# schmatic.net
KiCad netlist of a schematic drawn in EAGLE
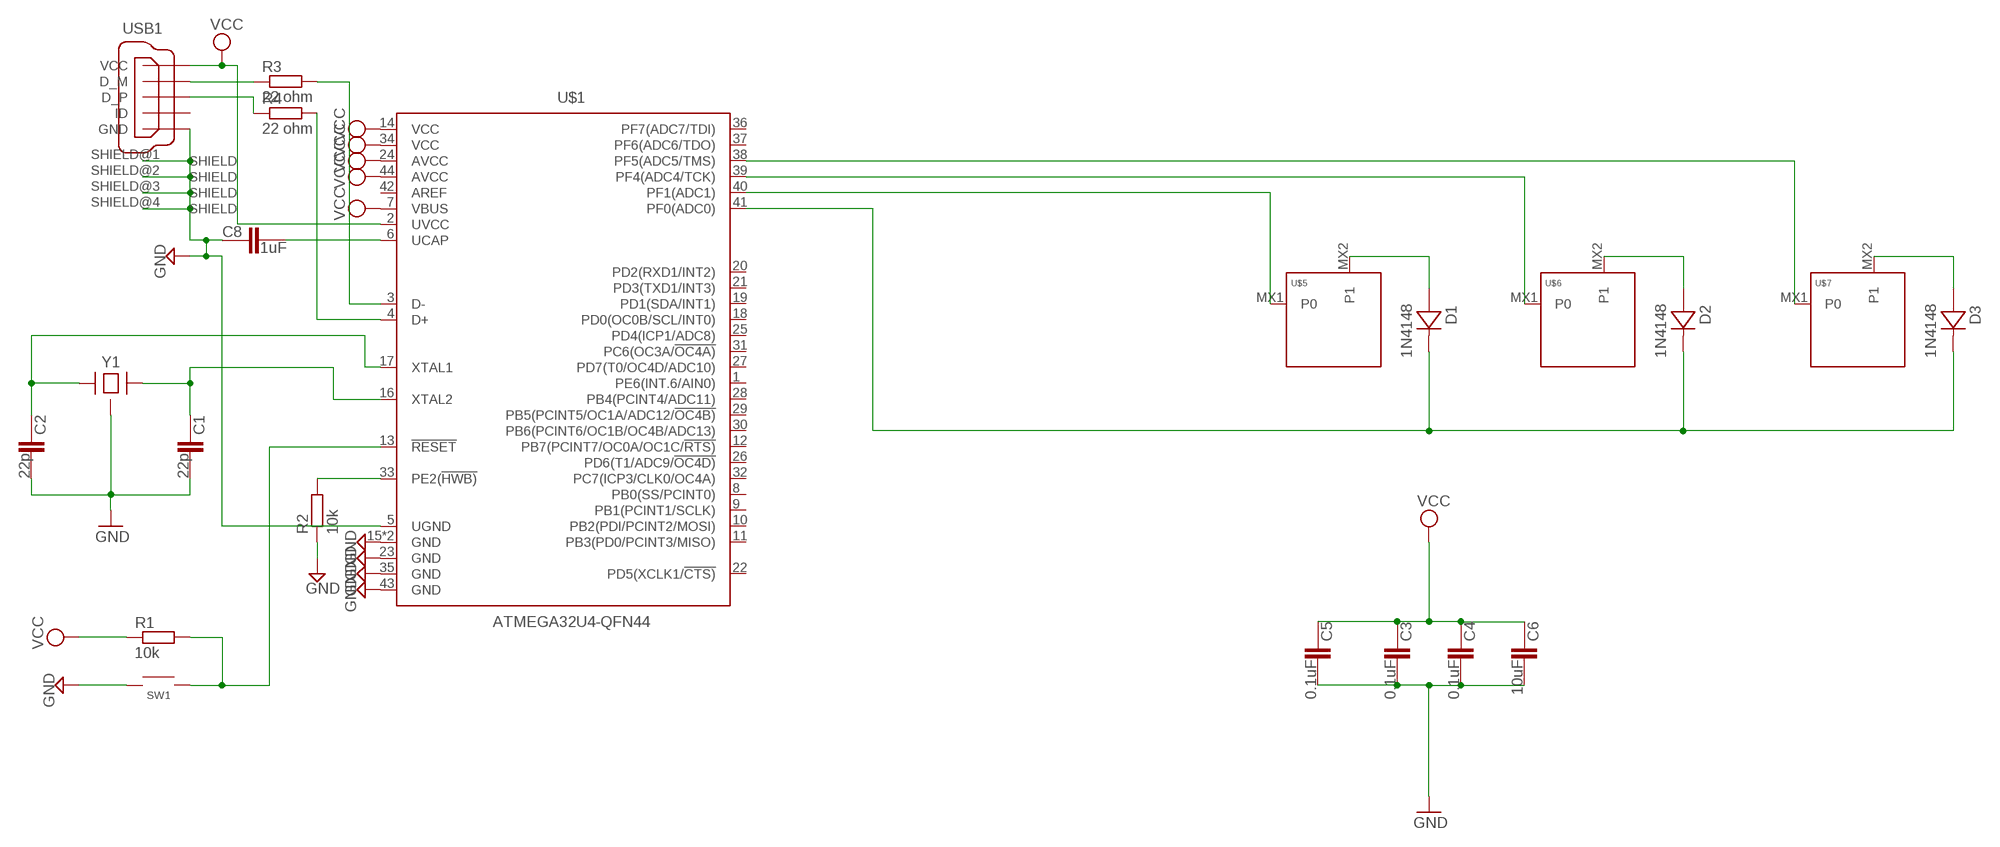
[diagram p0: schematic, sheet 1]

(export (version "E")
  (design (tool "Eeschema 10.0.6"))
  (components
    (comp (ref "C1")
      (value "22p")
      (footprint "eagle-import:C0402")
      (libsource (lib "eagle-import") (part "CAPACITOR-0402"))
    )
    (comp (ref "C2")
      (value "22p")
      (footprint "eagle-import:C0402")
      (libsource (lib "eagle-import") (part "CAPACITOR-0402"))
    )
    (comp (ref "C3")
      (value "0.1uF")
      (footprint "eagle-import:C0402")
      (libsource (lib "eagle-import") (part "CAPACITOR-0402"))
    )
    (comp (ref "C4")
      (value "0.1uF")
      (footprint "eagle-import:C0402")
      (libsource (lib "eagle-import") (part "CAPACITOR-0402"))
    )
    (comp (ref "C5")
      (value "0.1uF")
      (footprint "eagle-import:C0402")
      (libsource (lib "eagle-import") (part "CAPACITOR-0402"))
    )
    (comp (ref "C6")
      (value "10uF")
      (footprint "eagle-import:C0402")
      (libsource (lib "eagle-import") (part "CAPACITOR-0402"))
    )
    (comp (ref "C8")
      (value "1uF")
      (footprint "eagle-import:C0402")
      (libsource (lib "eagle-import") (part "CAPACITOR-0402"))
    )
    (comp (ref "D1")
      (value "1N4148")
      (footprint "eagle-import:DO-35")
      (libsource (lib "eagle-import") (part "DIODE-DO-35"))
    )
    (comp (ref "D2")
      (value "1N4148")
      (footprint "eagle-import:DO-35")
      (libsource (lib "eagle-import") (part "DIODE-DO-35"))
    )
    (comp (ref "D3")
      (value "1N4148")
      (footprint "eagle-import:DO-35")
      (libsource (lib "eagle-import") (part "DIODE-DO-35"))
    )
    (comp (ref "R1")
      (value "10k")
      (footprint "eagle-import:R0402")
      (libsource (lib "eagle-import") (part "RESISTOR-0405"))
    )
    (comp (ref "R2")
      (value "10k")
      (footprint "eagle-import:R0402")
      (libsource (lib "eagle-import") (part "RESISTOR-0405"))
    )
    (comp (ref "R3")
      (value "22 ohm")
      (footprint "eagle-import:R0402")
      (libsource (lib "eagle-import") (part "RESISTOR-0405"))
    )
    (comp (ref "R4")
      (value "22 ohm")
      (footprint "eagle-import:R0402")
      (libsource (lib "eagle-import") (part "RESISTOR-0405"))
    )
    (comp (ref "SW1")
      (value "SWITCH-SMD-EVQP-P2602W")
      (footprint "eagle-import:SWITCH-SMD-EVQP-P2602W")
      (libsource (lib "eagle-import") (part "SWITCH-SMD-EVQP-P2602W"))
    )
    (comp (ref "U$1")
      (value "ATMEGA32U4-QFN44")
      (footprint "eagle-import:QFN-44")
      (libsource (lib "eagle-import") (part "ATMEGA32U4-QFN44"))
    )
    (comp (ref "U$5")
      (value "KEYSWITCH-PLAIN-MXHSPCB-1U")
      (footprint "eagle-import:MXHSPCB-1U")
      (libsource (lib "eagle-import") (part "KEYSWITCH-PLAIN-MXHSPCB-1U"))
    )
    (comp (ref "U$6")
      (value "KEYSWITCH-PLAIN-MXHSPCB-1U")
      (footprint "eagle-import:MXHSPCB-1U")
      (libsource (lib "eagle-import") (part "KEYSWITCH-PLAIN-MXHSPCB-1U"))
    )
    (comp (ref "U$7")
      (value "KEYSWITCH-PLAIN-MXHSPCB-1U")
      (footprint "eagle-import:MXHSPCB-1U")
      (libsource (lib "eagle-import") (part "KEYSWITCH-PLAIN-MXHSPCB-1U"))
    )
    (comp (ref "USB1")
      (value "USB_CONN-MICRO-FEMALE")
      (footprint "eagle-import:ZB62D-B-5PA8")
      (libsource (lib "eagle-import") (part "USB_CONN-MICRO-FEMALE"))
    )
    (comp (ref "Y1")
      (value "CRYSTAL-4PIN-3.2X2.5")
      (footprint "eagle-import:CRYSTAL-3.2X2.5")
      (libsource (lib "eagle-import") (part "CRYSTAL-4PIN-3.2X2.5"))
    )
  )
  (nets
    (net (code "1") (name "GND") (class "Default")
      (node (ref "C1") (pin "2") (pinfunction "2_2") (pintype "passive"))
      (node (ref "C2") (pin "2") (pinfunction "2_2") (pintype "passive"))
      (node (ref "C3") (pin "2") (pinfunction "2_2") (pintype "passive"))
      (node (ref "C4") (pin "2") (pinfunction "2_2") (pintype "passive"))
      (node (ref "C5") (pin "2") (pinfunction "2_2") (pintype "passive"))
      (node (ref "C6") (pin "2") (pinfunction "2_2") (pintype "passive"))
      (node (ref "C8") (pin "1") (pinfunction "1_1") (pintype "passive"))
      (node (ref "R2") (pin "1") (pinfunction "1_1") (pintype "passive"))
      (node (ref "SW1") (pin "1A") (pinfunction "1_1A") (pintype "passive"))
      (node (ref "SW1") (pin "1B") (pinfunction "1_1B") (pintype "passive"))
      (node (ref "U$1") (pin "15") (pinfunction "GND_15") (pintype "bidirectional"))
      (node (ref "U$1") (pin "23") (pinfunction "GND_23") (pintype "bidirectional"))
      (node (ref "U$1") (pin "35") (pinfunction "GND_35") (pintype "bidirectional"))
      (node (ref "U$1") (pin "43") (pinfunction "GND_43") (pintype "bidirectional"))
      (node (ref "U$1") (pin "5") (pinfunction "UGND_5") (pintype "bidirectional"))
      (node (ref "U$1") (pin "TAB") (pinfunction "GND_TAB") (pintype "bidirectional"))
      (node (ref "USB1") (pin "5") (pinfunction "GND_5") (pintype "input"))
      (node (ref "USB1") (pin "SHIELD@1") (pinfunction "SHIELD_SHIELD@1") (pintype "bidirectional"))
      (node (ref "USB1") (pin "SHIELD@2") (pinfunction "SHIELD_SHIELD@2") (pintype "bidirectional"))
      (node (ref "USB1") (pin "SHIELD@3") (pinfunction "SHIELD_SHIELD@3") (pintype "bidirectional"))
      (node (ref "USB1") (pin "SHIELD@4") (pinfunction "SHIELD_SHIELD@4") (pintype "bidirectional"))
      (node (ref "Y1") (pin "2") (pinfunction "GND_2") (pintype "bidirectional"))
      (node (ref "Y1") (pin "4") (pinfunction "GND_4") (pintype "bidirectional"))
    )
    (net (code "2") (name "Net-(U$1-D+)") (class "Default")
      (node (ref "R4") (pin "2") (pinfunction "2_2") (pintype "passive"))
      (node (ref "U$1") (pin "4") (pinfunction "D+_4") (pintype "bidirectional"))
    )
    (net (code "3") (name "Net-(U$1-D-)") (class "Default")
      (node (ref "R3") (pin "2") (pinfunction "2_2") (pintype "passive"))
      (node (ref "U$1") (pin "3") (pinfunction "D-_3") (pintype "bidirectional"))
    )
    (net (code "4") (name "Net-(U$1-PE2(~{HWB}))") (class "Default")
      (node (ref "R2") (pin "2") (pinfunction "2_2") (pintype "passive"))
      (node (ref "U$1") (pin "33") (pinfunction "PE2(~{HWB})_33") (pintype "bidirectional"))
    )
    (net (code "5") (name "Net-(U$1-PF0(ADC0))") (class "Default")
      (node (ref "D1") (pin "C") (pinfunction "C_C") (pintype "passive"))
      (node (ref "D2") (pin "C") (pinfunction "C_C") (pintype "passive"))
      (node (ref "D3") (pin "C") (pinfunction "C_C") (pintype "passive"))
      (node (ref "U$1") (pin "41") (pinfunction "PF0(ADC0)_41") (pintype "bidirectional"))
    )
    (net (code "6") (name "Net-(U$1-PF1(ADC1))") (class "Default")
      (node (ref "U$1") (pin "40") (pinfunction "PF1(ADC1)_40") (pintype "bidirectional"))
      (node (ref "U$5") (pin "MX1") (pinfunction "P0_MX1") (pintype "bidirectional"))
    )
    (net (code "7") (name "Net-(U$1-PF4(ADC4{slash}TCK))") (class "Default")
      (node (ref "U$1") (pin "39") (pinfunction "PF4(ADC4/TCK)_39") (pintype "bidirectional"))
      (node (ref "U$6") (pin "MX1") (pinfunction "P0_MX1") (pintype "bidirectional"))
    )
    (net (code "8") (name "Net-(U$1-PF5(ADC5{slash}TMS))") (class "Default")
      (node (ref "U$1") (pin "38") (pinfunction "PF5(ADC5/TMS)_38") (pintype "bidirectional"))
      (node (ref "U$7") (pin "MX1") (pinfunction "P0_MX1") (pintype "bidirectional"))
    )
    (net (code "9") (name "Net-(U$1-UCAP)") (class "Default")
      (node (ref "C8") (pin "2") (pinfunction "2_2") (pintype "passive"))
      (node (ref "U$1") (pin "6") (pinfunction "UCAP_6") (pintype "bidirectional"))
    )
    (net (code "10") (name "Net-(U$1-XTAL1)") (class "Default")
      (node (ref "C2") (pin "1") (pinfunction "1_1") (pintype "passive"))
      (node (ref "U$1") (pin "17") (pinfunction "XTAL1_17") (pintype "bidirectional"))
      (node (ref "Y1") (pin "1") (pinfunction "1_1") (pintype "passive"))
    )
    (net (code "11") (name "Net-(U$1-XTAL2)") (class "Default")
      (node (ref "C1") (pin "1") (pinfunction "1_1") (pintype "passive"))
      (node (ref "U$1") (pin "16") (pinfunction "XTAL2_16") (pintype "bidirectional"))
      (node (ref "Y1") (pin "3") (pinfunction "2_3") (pintype "passive"))
    )
    (net (code "12") (name "Net-(U$1-~{RESET})") (class "Default")
      (node (ref "R1") (pin "2") (pinfunction "2_2") (pintype "passive"))
      (node (ref "SW1") (pin "2A") (pinfunction "2_2A") (pintype "passive"))
      (node (ref "SW1") (pin "2B") (pinfunction "2_2B") (pintype "passive"))
      (node (ref "U$1") (pin "13") (pinfunction "~{RESET}_13") (pintype "bidirectional"))
    )
    (net (code "13") (name "Net-(U$5-P1)") (class "Default")
      (node (ref "D1") (pin "A") (pinfunction "A_A") (pintype "passive"))
      (node (ref "U$5") (pin "MX2") (pinfunction "P1_MX2") (pintype "bidirectional"))
    )
    (net (code "14") (name "Net-(U$6-P1)") (class "Default")
      (node (ref "D2") (pin "A") (pinfunction "A_A") (pintype "passive"))
      (node (ref "U$6") (pin "MX2") (pinfunction "P1_MX2") (pintype "bidirectional"))
    )
    (net (code "15") (name "Net-(U$7-P1)") (class "Default")
      (node (ref "D3") (pin "A") (pinfunction "A_A") (pintype "passive"))
      (node (ref "U$7") (pin "MX2") (pinfunction "P1_MX2") (pintype "bidirectional"))
    )
    (net (code "16") (name "Net-(USB1-D_M)") (class "Default")
      (node (ref "R3") (pin "1") (pinfunction "1_1") (pintype "passive"))
      (node (ref "USB1") (pin "2") (pinfunction "D_M_2") (pintype "input"))
    )
    (net (code "17") (name "Net-(USB1-D_P)") (class "Default")
      (node (ref "R4") (pin "1") (pinfunction "1_1") (pintype "passive"))
      (node (ref "USB1") (pin "3") (pinfunction "D_P_3") (pintype "input"))
    )
    (net (code "18") (name "VCC") (class "Default")
      (node (ref "C3") (pin "1") (pinfunction "1_1") (pintype "passive"))
      (node (ref "C4") (pin "1") (pinfunction "1_1") (pintype "passive"))
      (node (ref "C5") (pin "1") (pinfunction "1_1") (pintype "passive"))
      (node (ref "C6") (pin "1") (pinfunction "1_1") (pintype "passive"))
      (node (ref "R1") (pin "1") (pinfunction "1_1") (pintype "passive"))
      (node (ref "U$1") (pin "14") (pinfunction "VCC_14") (pintype "bidirectional"))
      (node (ref "U$1") (pin "2") (pinfunction "UVCC_2") (pintype "bidirectional"))
      (node (ref "U$1") (pin "24") (pinfunction "AVCC_24") (pintype "bidirectional"))
      (node (ref "U$1") (pin "34") (pinfunction "VCC_34") (pintype "bidirectional"))
      (node (ref "U$1") (pin "44") (pinfunction "AVCC_44") (pintype "bidirectional"))
      (node (ref "U$1") (pin "7") (pinfunction "VBUS_7") (pintype "bidirectional"))
      (node (ref "USB1") (pin "1") (pinfunction "VCC_1") (pintype "input"))
    )
    (net (code "19") (name "unconnected-(U$1-AREF-Pad42)") (class "Default")
      (node (ref "U$1") (pin "42") (pinfunction "AREF_42") (pintype "bidirectional"))
    )
    (net (code "20") (name "unconnected-(U$1-PB0(SS{slash}PCINT0)-Pad8)") (class "Default")
      (node (ref "U$1") (pin "8") (pinfunction "PB0(SS/PCINT0)_8") (pintype "bidirectional"))
    )
    (net (code "21") (name "unconnected-(U$1-PB1(PCINT1{slash}SCLK)-Pad9)") (class "Default")
      (node (ref "U$1") (pin "9") (pinfunction "PB1(PCINT1/SCLK)_9") (pintype "bidirectional"))
    )
    (net (code "22") (name "unconnected-(U$1-PB2(PDI{slash}PCINT2{slash}MOSI)-Pad10)") (class "Default")
      (node (ref "U$1") (pin "10") (pinfunction "PB2(PDI/PCINT2/MOSI)_10") (pintype "bidirectional"))
    )
    (net (code "23") (name "unconnected-(U$1-PB3(PD0{slash}PCINT3{slash}MISO)-Pad11)") (class "Default")
      (node (ref "U$1") (pin "11") (pinfunction "PB3(PD0/PCINT3/MISO)_11") (pintype "bidirectional"))
    )
    (net (code "24") (name "unconnected-(U$1-PB4(PCINT4{slash}ADC11)-Pad28)") (class "Default")
      (node (ref "U$1") (pin "28") (pinfunction "PB4(PCINT4/ADC11)_28") (pintype "bidirectional"))
    )
    (net (code "25") (name "unconnected-(U$1-PB5(PCINT5{slash}OC1A{slash}ADC12{slash}~{OC4B})-Pad29)") (class "Default")
      (node (ref "U$1") (pin "29") (pinfunction "PB5(PCINT5/OC1A/ADC12/~{OC4B})_29") (pintype "bidirectional"))
    )
    (net (code "26") (name "unconnected-(U$1-PB6(PCINT6{slash}OC1B{slash}OC4B{slash}ADC13)-Pad30)") (class "Default")
      (node (ref "U$1") (pin "30") (pinfunction "PB6(PCINT6/OC1B/OC4B/ADC13)_30") (pintype "bidirectional"))
    )
    (net (code "27") (name "unconnected-(U$1-PB7(PCINT7{slash}OC0A{slash}OC1C{slash}~{RTS})-Pad12)") (class "Default")
      (node (ref "U$1") (pin "12") (pinfunction "PB7(PCINT7/OC0A/OC1C/~{RTS})_12") (pintype "bidirectional"))
    )
    (net (code "28") (name "unconnected-(U$1-PC6(OC3A{slash}~{OC4A})-Pad31)") (class "Default")
      (node (ref "U$1") (pin "31") (pinfunction "PC6(OC3A/~{OC4A})_31") (pintype "bidirectional"))
    )
    (net (code "29") (name "unconnected-(U$1-PC7(ICP3{slash}CLK0{slash}OC4A)-Pad32)") (class "Default")
      (node (ref "U$1") (pin "32") (pinfunction "PC7(ICP3/CLK0/OC4A)_32") (pintype "bidirectional"))
    )
    (net (code "30") (name "unconnected-(U$1-PD0(OC0B{slash}SCL{slash}INT0)-Pad18)") (class "Default")
      (node (ref "U$1") (pin "18") (pinfunction "PD0(OC0B/SCL/INT0)_18") (pintype "bidirectional"))
    )
    (net (code "31") (name "unconnected-(U$1-PD1(SDA{slash}INT1)-Pad19)") (class "Default")
      (node (ref "U$1") (pin "19") (pinfunction "PD1(SDA/INT1)_19") (pintype "bidirectional"))
    )
    (net (code "32") (name "unconnected-(U$1-PD2(RXD1{slash}INT2)-Pad20)") (class "Default")
      (node (ref "U$1") (pin "20") (pinfunction "PD2(RXD1/INT2)_20") (pintype "bidirectional"))
    )
    (net (code "33") (name "unconnected-(U$1-PD3(TXD1{slash}INT3)-Pad21)") (class "Default")
      (node (ref "U$1") (pin "21") (pinfunction "PD3(TXD1/INT3)_21") (pintype "bidirectional"))
    )
    (net (code "34") (name "unconnected-(U$1-PD4(ICP1{slash}ADC8)-Pad25)") (class "Default")
      (node (ref "U$1") (pin "25") (pinfunction "PD4(ICP1/ADC8)_25") (pintype "bidirectional"))
    )
    (net (code "35") (name "unconnected-(U$1-PD5(XCLK1{slash}~{CTS})-Pad22)") (class "Default")
      (node (ref "U$1") (pin "22") (pinfunction "PD5(XCLK1/~{CTS})_22") (pintype "bidirectional"))
    )
    (net (code "36") (name "unconnected-(U$1-PD6(T1{slash}ADC9{slash}~{OC4D})-Pad26)") (class "Default")
      (node (ref "U$1") (pin "26") (pinfunction "PD6(T1/ADC9/~{OC4D})_26") (pintype "bidirectional"))
    )
    (net (code "37") (name "unconnected-(U$1-PD7(T0{slash}OC4D{slash}ADC10)-Pad27)") (class "Default")
      (node (ref "U$1") (pin "27") (pinfunction "PD7(T0/OC4D/ADC10)_27") (pintype "bidirectional"))
    )
    (net (code "38") (name "unconnected-(U$1-PE6(INT.6{slash}AIN0)-Pad1)") (class "Default")
      (node (ref "U$1") (pin "1") (pinfunction "PE6(INT.6/AIN0)_1") (pintype "bidirectional"))
    )
    (net (code "39") (name "unconnected-(U$1-PF6(ADC6{slash}TDO)-Pad37)") (class "Default")
      (node (ref "U$1") (pin "37") (pinfunction "PF6(ADC6/TDO)_37") (pintype "bidirectional"))
    )
    (net (code "40") (name "unconnected-(U$1-PF7(ADC7{slash}TDI)-Pad36)") (class "Default")
      (node (ref "U$1") (pin "36") (pinfunction "PF7(ADC7/TDI)_36") (pintype "bidirectional"))
    )
    (net (code "41") (name "unconnected-(USB1-ID-Pad4)") (class "Default")
      (node (ref "USB1") (pin "4") (pinfunction "ID_4") (pintype "input"))
    )
  )
)
